# nodeSensor.net
KiCad netlist of a schematic drawn in EAGLE
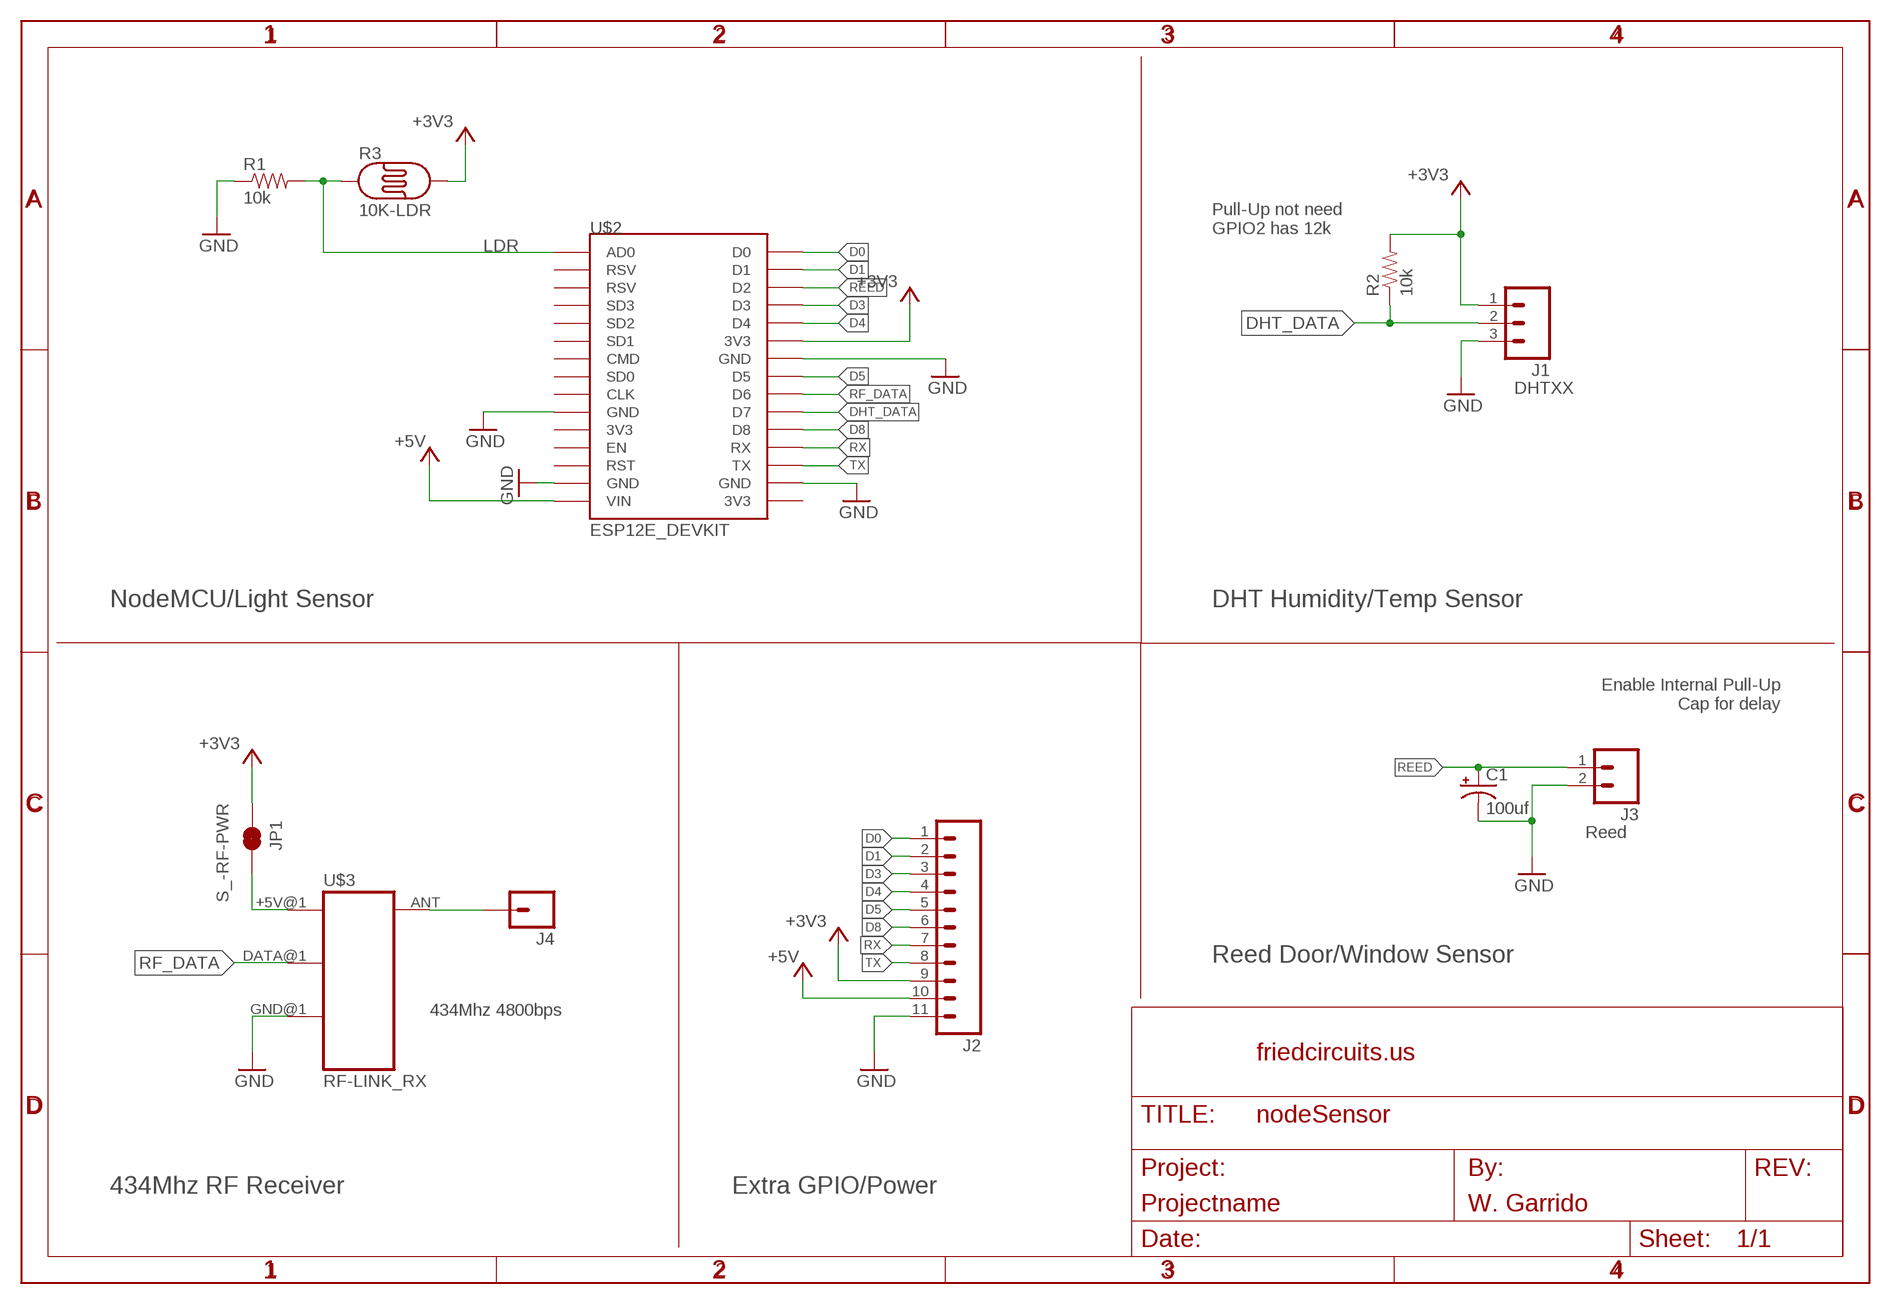
[diagram p0: schematic, sheet 1]

(export (version "E")
  (design (tool "Eeschema 10.0.6"))
  (components
    (comp (ref "C1")
      (value "100uf")
      (footprint "eagle-import:CPOL-RADIAL-1000UF-25V")
      (libsource (lib "eagle-import") (part "CAP_POLPTH4"))
    )
    (comp (ref "J1")
      (value "M03LOCK")
      (footprint "eagle-import:1X03_LOCK")
      (libsource (lib "eagle-import") (part "M03LOCK"))
    )
    (comp (ref "J2")
      (value "M11LOCK")
      (footprint "eagle-import:1X11_LOCK")
      (libsource (lib "eagle-import") (part "M11LOCK"))
    )
    (comp (ref "J3")
      (value "M02LOCK")
      (footprint "eagle-import:1X02_LOCK")
      (libsource (lib "eagle-import") (part "M02LOCK"))
    )
    (comp (ref "J4")
      (value "M01PTH_LONGPAD")
      (footprint "eagle-import:1X01_LONGPAD")
      (libsource (lib "eagle-import") (part "M01PTH_LONGPAD"))
    )
    (comp (ref "JP1")
      (value "S_-RF-PWR")
      (footprint "eagle-import:PAD-JUMPER-2-NC_BY_TRACE_YES_SILK")
      (libsource (lib "eagle-import") (part "JUMPER-PAD-2-NC_BY_TRACE"))
    )
    (comp (ref "R1")
      (value "10k")
      (footprint "eagle-import:AXIAL-0.3-KIT")
      (libsource (lib "eagle-import") (part "RESISTORKIT"))
    )
    (comp (ref "R2")
      (value "10k")
      (footprint "eagle-import:AXIAL-0.3-KIT")
      (libsource (lib "eagle-import") (part "RESISTORKIT"))
    )
    (comp (ref "R3")
      (value "10K-LDR")
      (footprint "eagle-import:PHOTOCELL")
      (libsource (lib "eagle-import") (part "PHOTOCELLPTH"))
    )
    (comp (ref "U$1")
      (value "FRAME_DINA4_L")
      (footprint "eagle-import:FC_CREDIT")
      (fields (field (name "AUTHOR") "W. Garrido"))
      (libsource (lib "eagle-import") (part "FRAME_DINA4_L"))
    )
    (comp (ref "U$2")
      (value "ESP12E_DEVKIT")
      (footprint "eagle-import:ESP12E_DEVKIT")
      (libsource (lib "eagle-import") (part "ESP12E_DEVKIT"))
    )
    (comp (ref "U$3")
      (value "RF-LINK_RX")
      (footprint "eagle-import:RF-LINK_RX")
      (libsource (lib "eagle-import") (part "RF-LINK_RX"))
    )
  )
  (nets
    (net (code "1") (name "+3V3") (class "Default")
      (node (ref "J1") (pin "1") (pinfunction "1_1") (pintype "passive"))
      (node (ref "J2") (pin "9") (pinfunction "9_9") (pintype "passive"))
      (node (ref "JP1") (pin "1") (pinfunction "1_1") (pintype "passive"))
      (node (ref "R2") (pin "P$2") (pinfunction "2_P$2") (pintype "passive"))
      (node (ref "R3") (pin "2") (pinfunction "P$2_2") (pintype "bidirectional"))
      (node (ref "U$2") (pin "3V3@1") (pinfunction "3V3_3V3@1") (pintype "bidirectional"))
    )
    (net (code "2") (name "+5V") (class "Default")
      (node (ref "J2") (pin "10") (pinfunction "10_10") (pintype "passive"))
      (node (ref "U$2") (pin "VIN") (pinfunction "VIN_VIN") (pintype "bidirectional"))
    )
    (net (code "3") (name "/LDR") (class "Default")
      (node (ref "R1") (pin "P$2") (pinfunction "2_P$2") (pintype "passive"))
      (node (ref "R3") (pin "1") (pinfunction "P$1_1") (pintype "bidirectional"))
      (node (ref "U$2") (pin "AD0") (pinfunction "AD0_AD0") (pintype "bidirectional"))
    )
    (net (code "4") (name "D0") (class "Default")
      (node (ref "J2") (pin "1") (pinfunction "1_1") (pintype "passive"))
      (node (ref "U$2") (pin "D0") (pinfunction "D0_D0") (pintype "bidirectional"))
    )
    (net (code "5") (name "D1") (class "Default")
      (node (ref "J2") (pin "2") (pinfunction "2_2") (pintype "passive"))
      (node (ref "U$2") (pin "D1") (pinfunction "D1_D1") (pintype "bidirectional"))
    )
    (net (code "6") (name "D3") (class "Default")
      (node (ref "J2") (pin "3") (pinfunction "3_3") (pintype "passive"))
      (node (ref "U$2") (pin "D3") (pinfunction "D3_D3") (pintype "bidirectional"))
    )
    (net (code "7") (name "D4") (class "Default")
      (node (ref "J2") (pin "4") (pinfunction "4_4") (pintype "passive"))
      (node (ref "U$2") (pin "D4") (pinfunction "D4_D4") (pintype "bidirectional"))
    )
    (net (code "8") (name "D5") (class "Default")
      (node (ref "J2") (pin "5") (pinfunction "5_5") (pintype "passive"))
      (node (ref "U$2") (pin "D5") (pinfunction "D5_D5") (pintype "bidirectional"))
    )
    (net (code "9") (name "D8") (class "Default")
      (node (ref "J2") (pin "6") (pinfunction "6_6") (pintype "passive"))
      (node (ref "U$2") (pin "D8") (pinfunction "D8_D8") (pintype "bidirectional"))
    )
    (net (code "10") (name "DHT_DATA") (class "Default")
      (node (ref "J1") (pin "2") (pinfunction "2_2") (pintype "passive"))
      (node (ref "R2") (pin "P$1") (pinfunction "1_P$1") (pintype "passive"))
      (node (ref "U$2") (pin "D7") (pinfunction "D7_D7") (pintype "bidirectional"))
    )
    (net (code "11") (name "GND") (class "Default")
      (node (ref "C1") (pin "2") (pinfunction "-_2") (pintype "passive"))
      (node (ref "J1") (pin "3") (pinfunction "3_3") (pintype "passive"))
      (node (ref "J2") (pin "11") (pinfunction "11_11") (pintype "passive"))
      (node (ref "J3") (pin "2") (pinfunction "2_2") (pintype "passive"))
      (node (ref "R1") (pin "P$1") (pinfunction "1_P$1") (pintype "passive"))
      (node (ref "U$2") (pin "GND@0") (pinfunction "GND_GND@0") (pintype "bidirectional"))
      (node (ref "U$2") (pin "GND@1") (pinfunction "GND_GND@1") (pintype "bidirectional"))
      (node (ref "U$2") (pin "GND@2") (pinfunction "GND_GND@2") (pintype "bidirectional"))
      (node (ref "U$2") (pin "GND@3") (pinfunction "GND_GND@3") (pintype "bidirectional"))
      (node (ref "U$3") (pin "GND@1") (pinfunction "GND_GND@1") (pintype "power_in"))
    )
    (net (code "12") (name "Net-(J4-Pad1)") (class "Default")
      (node (ref "J4") (pin "1") (pinfunction "1_1") (pintype "passive"))
      (node (ref "U$3") (pin "ANT") (pinfunction "ANT_ANT") (pintype "passive"))
    )
    (net (code "13") (name "Net-(U$3-+5V)") (class "Default")
      (node (ref "JP1") (pin "2") (pinfunction "2_2") (pintype "passive"))
      (node (ref "U$3") (pin "+5V@1") (pinfunction "+5V_+5V@1") (pintype "power_in"))
    )
    (net (code "14") (name "REED") (class "Default")
      (node (ref "C1") (pin "1") (pinfunction "+_1") (pintype "passive"))
      (node (ref "J3") (pin "1") (pinfunction "1_1") (pintype "passive"))
      (node (ref "U$2") (pin "D2") (pinfunction "D2_D2") (pintype "bidirectional"))
    )
    (net (code "15") (name "RF_DATA") (class "Default")
      (node (ref "U$2") (pin "D6") (pinfunction "D6_D6") (pintype "bidirectional"))
      (node (ref "U$3") (pin "DATA@1") (pinfunction "DATA_DATA@1") (pintype "input"))
    )
    (net (code "16") (name "RX") (class "Default")
      (node (ref "J2") (pin "7") (pinfunction "7_7") (pintype "passive"))
      (node (ref "U$2") (pin "RX") (pinfunction "RX_RX") (pintype "bidirectional"))
    )
    (net (code "17") (name "TX") (class "Default")
      (node (ref "J2") (pin "8") (pinfunction "8_8") (pintype "passive"))
      (node (ref "U$2") (pin "TX") (pinfunction "TX_TX") (pintype "bidirectional"))
    )
    (net (code "18") (name "unconnected-(U$2-3V3-Pad3V3@0)") (class "Default")
      (node (ref "U$2") (pin "3V3@0") (pinfunction "3V3_3V3@0") (pintype "bidirectional"))
    )
    (net (code "19") (name "unconnected-(U$2-3V3-Pad3V3@2)") (class "Default")
      (node (ref "U$2") (pin "3V3@2") (pinfunction "3V3_3V3@2") (pintype "bidirectional"))
    )
    (net (code "20") (name "unconnected-(U$2-PadCLK)") (class "Default")
      (node (ref "U$2") (pin "CLK") (pinfunction "CLK_CLK") (pintype "bidirectional"))
    )
    (net (code "21") (name "unconnected-(U$2-PadCMD)") (class "Default")
      (node (ref "U$2") (pin "CMD") (pinfunction "CMD_CMD") (pintype "bidirectional"))
    )
    (net (code "22") (name "unconnected-(U$2-PadEN)") (class "Default")
      (node (ref "U$2") (pin "EN") (pinfunction "EN_EN") (pintype "bidirectional"))
    )
    (net (code "23") (name "unconnected-(U$2-PadRST)") (class "Default")
      (node (ref "U$2") (pin "RST") (pinfunction "RST_RST") (pintype "bidirectional"))
    )
    (net (code "24") (name "unconnected-(U$2-PadSD0)") (class "Default")
      (node (ref "U$2") (pin "SD0") (pinfunction "SD0_SD0") (pintype "bidirectional"))
    )
    (net (code "25") (name "unconnected-(U$2-PadSD1)") (class "Default")
      (node (ref "U$2") (pin "SD1") (pinfunction "SD1_SD1") (pintype "bidirectional"))
    )
    (net (code "26") (name "unconnected-(U$2-PadSD2)") (class "Default")
      (node (ref "U$2") (pin "SD2") (pinfunction "SD2_SD2") (pintype "bidirectional"))
    )
    (net (code "27") (name "unconnected-(U$2-PadSD3)") (class "Default")
      (node (ref "U$2") (pin "SD3") (pinfunction "SD3_SD3") (pintype "bidirectional"))
    )
    (net (code "28") (name "unconnected-(U$2-RSV-PadRSV@0)") (class "Default")
      (node (ref "U$2") (pin "RSV@0") (pinfunction "RSV_RSV@0") (pintype "bidirectional"))
    )
    (net (code "29") (name "unconnected-(U$2-RSV-PadRSV@1)") (class "Default")
      (node (ref "U$2") (pin "RSV@1") (pinfunction "RSV_RSV@1") (pintype "bidirectional"))
    )
  )
)
